# F4.net
KiCad netlist of a schematic drawn in Altium Designer
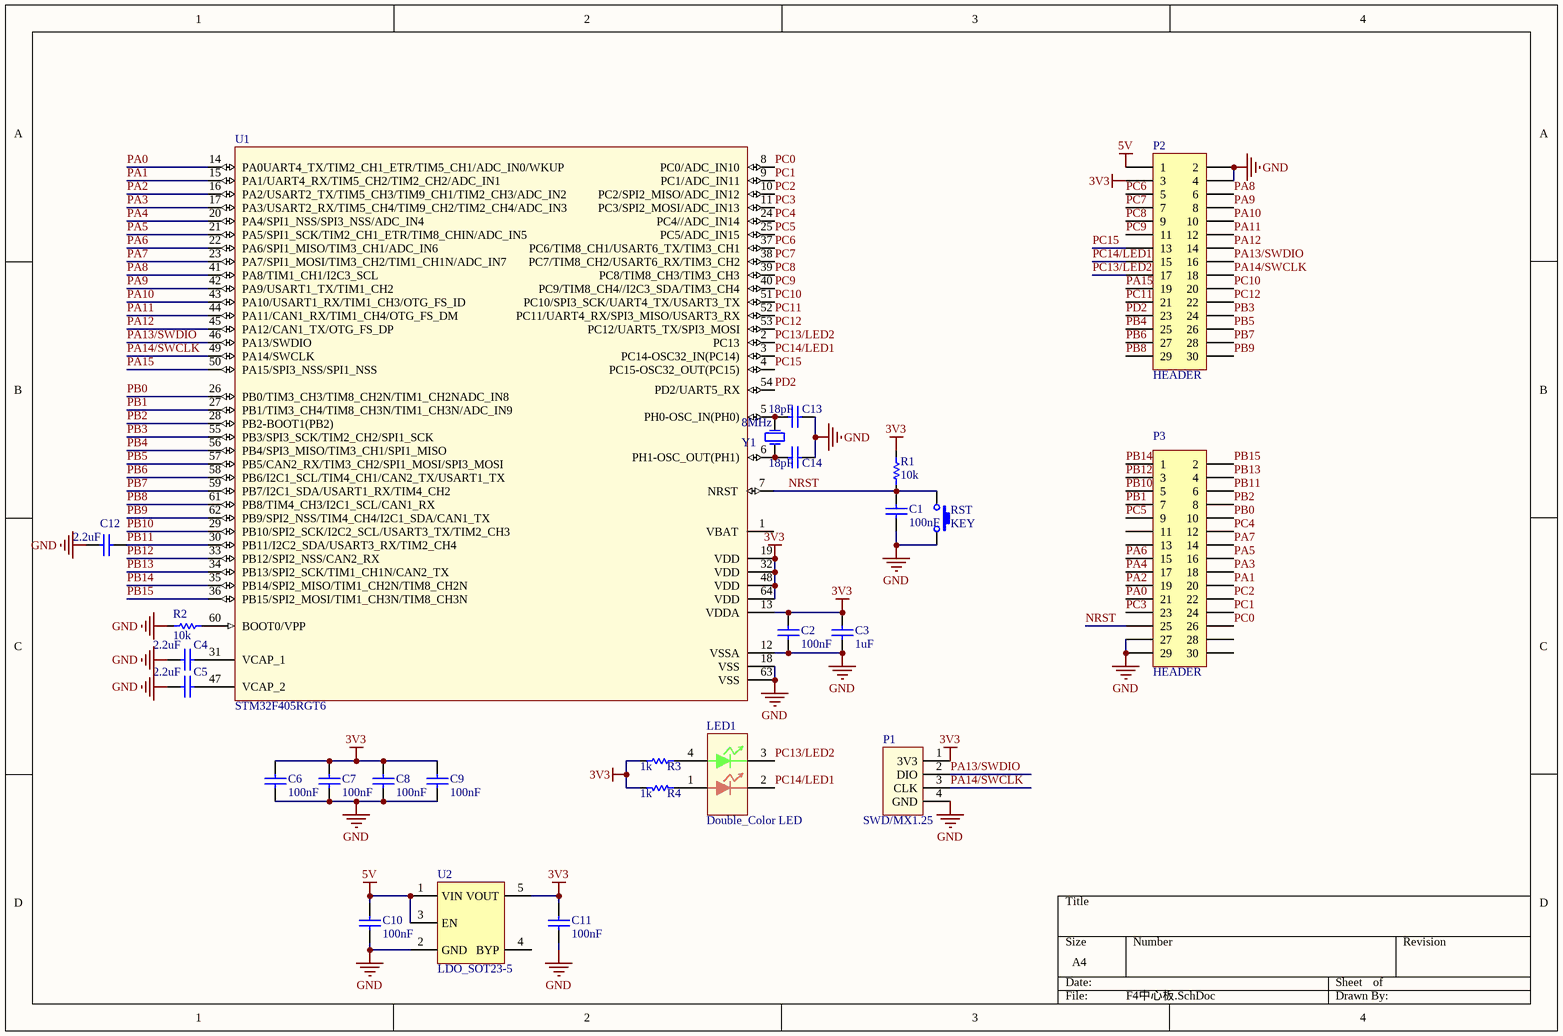
[diagram p0: F4中心板.SchDoc]

(export (version "E")
  (design (tool "Eeschema 10.0.6"))
  (components
    (comp (ref "C1")
      (value "100nF")
      (footprint "0603C")
      (description "Capacitor")
      (fields (field (name "PUBLISHER") "Altium Limited"))
      (libsource (lib "MyComponents_v2.5") (part "Cap"))
    )
    (comp (ref "C2")
      (value "100nF")
      (footprint "0603C")
      (description "Capacitor")
      (fields (field (name "PUBLISHER") "Altium Limited"))
      (libsource (lib "MyComponents_v2.5") (part "Cap"))
    )
    (comp (ref "C3")
      (value "1uF")
      (footprint "0603C")
      (description "Capacitor")
      (fields (field (name "PUBLISHER") "Altium Limited"))
      (libsource (lib "MyComponents_v2.5") (part "Cap"))
    )
    (comp (ref "C4")
      (value "2.2uF")
      (footprint "0603C")
      (description "Capacitor")
      (fields (field (name "PUBLISHER") "Altium Limited"))
      (libsource (lib "MyComponents_v2.5") (part "Cap"))
    )
    (comp (ref "C5")
      (value "2.2uF")
      (footprint "0603C")
      (description "Capacitor")
      (fields (field (name "PUBLISHER") "Altium Limited"))
      (libsource (lib "MyComponents_v2.5") (part "Cap"))
    )
    (comp (ref "C6")
      (value "100nF")
      (footprint "0603C")
      (description "Capacitor")
      (fields (field (name "PUBLISHER") "Altium Limited"))
      (libsource (lib "MyComponents_v2.5") (part "Cap"))
    )
    (comp (ref "C7")
      (value "100nF")
      (footprint "0603C")
      (description "Capacitor")
      (fields (field (name "PUBLISHER") "Altium Limited"))
      (libsource (lib "MyComponents_v2.5") (part "Cap"))
    )
    (comp (ref "C8")
      (value "100nF")
      (footprint "0603C")
      (description "Capacitor")
      (fields (field (name "PUBLISHER") "Altium Limited"))
      (libsource (lib "MyComponents_v2.5") (part "Cap"))
    )
    (comp (ref "C9")
      (value "100nF")
      (footprint "0603C")
      (description "Capacitor")
      (fields (field (name "PUBLISHER") "Altium Limited"))
      (libsource (lib "MyComponents_v2.5") (part "Cap"))
    )
    (comp (ref "C10")
      (value "100nF")
      (footprint "0603C")
      (description "Capacitor")
      (fields (field (name "PUBLISHER") "Altium Limited"))
      (libsource (lib "MyComponents_v2.5") (part "Cap"))
    )
    (comp (ref "C11")
      (value "100nF")
      (footprint "0603C")
      (description "Capacitor")
      (fields (field (name "PUBLISHER") "Altium Limited"))
      (libsource (lib "MyComponents_v2.5") (part "Cap"))
    )
    (comp (ref "C12")
      (value "2.2uF")
      (footprint "0603C")
      (description "Capacitor")
      (fields (field (name "PUBLISHER") "Altium Limited"))
      (libsource (lib "MyComponents_v2.5") (part "Cap"))
    )
    (comp (ref "C13")
      (value "18pF")
      (footprint "0603C")
      (description "Capacitor")
      (fields (field (name "PUBLISHER") "Altium Limited"))
      (libsource (lib "MyComponents_v2.5") (part "Cap"))
    )
    (comp (ref "C14")
      (value "18pF")
      (footprint "0603C")
      (description "Capacitor")
      (fields (field (name "PUBLISHER") "Altium Limited"))
      (libsource (lib "MyComponents_v2.5") (part "Cap"))
    )
    (comp (ref "LED1")
      (value "Double_Color LED")
      (footprint "0805LEDX2")
      (libsource (lib "MyComponents_v2.5") (part "Double_Color LED"))
    )
    (comp (ref "P1")
      (value "SWD/MX1.25")
      (footprint "A1.25AW-4P")
      (libsource (lib "MyComponents_v2.5") (part "SWD_HEADER"))
    )
    (comp (ref "P2")
      (value "HEADER")
      (footprint "HEADER 15x2 SMT 1.27MM")
      (description "15X2 header")
      (libsource (lib "MyComponents_v2.5") (part "HEADER 15x2"))
    )
    (comp (ref "P3")
      (value "HEADER")
      (footprint "HEADER 15x2 SMT 1.27MM")
      (description "15X2 header")
      (libsource (lib "MyComponents_v2.5") (part "HEADER 15x2"))
    )
    (comp (ref "R1")
      (value "10k")
      (footprint "0603R")
      (description "Resistor")
      (fields (field (name "PUBLISHER") "Altium Limited"))
      (libsource (lib "MyComponents_v2.5") (part "Res1"))
    )
    (comp (ref "R2")
      (value "10k")
      (footprint "0603R")
      (description "Resistor")
      (fields (field (name "PUBLISHER") "Altium Limited"))
      (libsource (lib "MyComponents_v2.5") (part "Res1"))
    )
    (comp (ref "R3")
      (value "1k")
      (footprint "0603R")
      (description "Resistor")
      (fields (field (name "PUBLISHER") "Altium Limited"))
      (libsource (lib "MyComponents_v2.5") (part "Res1"))
    )
    (comp (ref "R4")
      (value "1k")
      (footprint "0603R")
      (description "Resistor")
      (fields (field (name "PUBLISHER") "Altium Limited"))
      (libsource (lib "MyComponents_v2.5") (part "Res1"))
    )
    (comp (ref "RST")
      (value "KEY")
      (footprint "SW 3mmx4mm")
      (description "Button")
      (fields (field (name "PUBLISHER") "Altium Limited"))
      (libsource (lib "MyComponents_v2.5") (part "PushButton_2p"))
    )
    (comp (ref "U1")
      (value "STM32F405RGT6")
      (footprint "LQFP_64")
      (libsource (lib "MyComponents_v2.5") (part "STM32F405RGT6_detail_1"))
    )
    (comp (ref "U2")
      (value "LDO_SOT23-5")
      (footprint "SOT-23-5 L")
      (libsource (lib "MyComponents_v2.5") (part "LDO_SOT23-5"))
    )
    (comp (ref "Y1")
      (value "8MHz")
      (footprint "NX3225GD")
      (description "Crystal Oscillator")
      (fields (field (name "PUBLISHER") "Altium Limited"))
      (libsource (lib "MyComponents_v2.5") (part "XTAL"))
    )
  )
  (nets
    (net (code "1") (name "/NRST") (class "Default")
      (node (ref "C1") (pin "2") (pinfunction "2_2") (pintype "passive"))
      (node (ref "P3") (pin "25") (pinfunction "25_25") (pintype "passive"))
      (node (ref "R1") (pin "1") (pinfunction "1_1") (pintype "passive"))
      (node (ref "RST") (pin "1") (pinfunction "1_1") (pintype "passive"))
      (node (ref "U1") (pin "7") (pinfunction "NRST_7") (pintype "bidirectional"))
    )
    (net (code "2") (name "/PA0") (class "Default")
      (node (ref "P3") (pin "21") (pinfunction "21_21") (pintype "passive"))
      (node (ref "U1") (pin "14") (pinfunction "PA0UART4_TX/TIM2_CH1_ETR/TIM5_CH1/ADC_IN0/WKUP_14") (pintype "bidirectional"))
    )
    (net (code "3") (name "/PA1") (class "Default")
      (node (ref "P3") (pin "20") (pinfunction "20_20") (pintype "passive"))
      (node (ref "U1") (pin "15") (pinfunction "PA1/UART4_RX/TIM5_CH2/TIM2_CH2/ADC_IN1_15") (pintype "bidirectional"))
    )
    (net (code "4") (name "/PA2") (class "Default")
      (node (ref "P3") (pin "19") (pinfunction "19_19") (pintype "passive"))
      (node (ref "U1") (pin "16") (pinfunction "PA2/USART2_TX/TIM5_CH3/TIM9_CH1/TIM2_CH3/ADC_IN2_16") (pintype "bidirectional"))
    )
    (net (code "5") (name "/PA3") (class "Default")
      (node (ref "P3") (pin "18") (pinfunction "18_18") (pintype "passive"))
      (node (ref "U1") (pin "17") (pinfunction "PA3/USART2_RX/TIM5_CH4/TIM9_CH2/TIM2_CH4/ADC_IN3_17") (pintype "bidirectional"))
    )
    (net (code "6") (name "/PA4") (class "Default")
      (node (ref "P3") (pin "17") (pinfunction "17_17") (pintype "passive"))
      (node (ref "U1") (pin "20") (pinfunction "PA4/SPI1_NSS/SPI3_NSS/ADC_IN4_20") (pintype "bidirectional"))
    )
    (net (code "7") (name "/PA5") (class "Default")
      (node (ref "P3") (pin "16") (pinfunction "16_16") (pintype "passive"))
      (node (ref "U1") (pin "21") (pinfunction "PA5/SPI1_SCK/TIM2_CH1_ETR/TIM8_CHIN/ADC_IN5_21") (pintype "bidirectional"))
    )
    (net (code "8") (name "/PA6") (class "Default")
      (node (ref "P3") (pin "15") (pinfunction "15_15") (pintype "passive"))
      (node (ref "U1") (pin "22") (pinfunction "PA6/SPI1_MISO/TIM3_CH1/ADC_IN6_22") (pintype "bidirectional"))
    )
    (net (code "9") (name "/PA7") (class "Default")
      (node (ref "P3") (pin "14") (pinfunction "14_14") (pintype "passive"))
      (node (ref "U1") (pin "23") (pinfunction "PA7/SPI1_MOSI/TIM3_CH2/TIM1_CH1N/ADC_IN7_23") (pintype "bidirectional"))
    )
    (net (code "10") (name "/PA8") (class "Default")
      (node (ref "P2") (pin "6") (pinfunction "6_6") (pintype "passive"))
      (node (ref "U1") (pin "41") (pinfunction "PA8/TIM1_CH1/I2C3_SCL_41") (pintype "bidirectional"))
    )
    (net (code "11") (name "/PA9") (class "Default")
      (node (ref "P2") (pin "8") (pinfunction "8_8") (pintype "passive"))
      (node (ref "U1") (pin "42") (pinfunction "PA9/USART1_TX/TIM1_CH2_42") (pintype "bidirectional"))
    )
    (net (code "12") (name "/PA10") (class "Default")
      (node (ref "P2") (pin "10") (pinfunction "10_10") (pintype "passive"))
      (node (ref "U1") (pin "43") (pinfunction "PA10/USART1_RX/TIM1_CH3/OTG_FS_ID_43") (pintype "bidirectional"))
    )
    (net (code "13") (name "/PA11") (class "Default")
      (node (ref "P2") (pin "12") (pinfunction "12_12") (pintype "passive"))
      (node (ref "U1") (pin "44") (pinfunction "PA11/CAN1_RX/TIM1_CH4/OTG_FS_DM_44") (pintype "bidirectional"))
    )
    (net (code "14") (name "/PA12") (class "Default")
      (node (ref "P2") (pin "14") (pinfunction "14_14") (pintype "passive"))
      (node (ref "U1") (pin "45") (pinfunction "PA12/CAN1_TX/OTG_FS_DP_45") (pintype "bidirectional"))
    )
    (net (code "15") (name "/PA13{slash}SWDIO") (class "Default")
      (node (ref "P1") (pin "2") (pinfunction "DIO_2") (pintype "passive"))
      (node (ref "P2") (pin "16") (pinfunction "16_16") (pintype "passive"))
      (node (ref "U1") (pin "46") (pinfunction "PA13/SWDIO_46") (pintype "bidirectional"))
    )
    (net (code "16") (name "/PA14{slash}SWCLK") (class "Default")
      (node (ref "P1") (pin "3") (pinfunction "CLK_3") (pintype "passive"))
      (node (ref "P2") (pin "18") (pinfunction "18_18") (pintype "passive"))
      (node (ref "U1") (pin "49") (pinfunction "PA14/SWCLK_49") (pintype "bidirectional"))
    )
    (net (code "17") (name "/PA15") (class "Default")
      (node (ref "P2") (pin "19") (pinfunction "19_19") (pintype "passive"))
      (node (ref "U1") (pin "50") (pinfunction "PA15/SPI3_NSS/SPI1_NSS_50") (pintype "bidirectional"))
    )
    (net (code "18") (name "/PB0") (class "Default")
      (node (ref "P3") (pin "10") (pinfunction "10_10") (pintype "passive"))
      (node (ref "U1") (pin "26") (pinfunction "PB0/TIM3_CH3/TIM8_CH2N/TIM1_CH2NADC_IN8_26") (pintype "bidirectional"))
    )
    (net (code "19") (name "/PB1") (class "Default")
      (node (ref "P3") (pin "7") (pinfunction "7_7") (pintype "passive"))
      (node (ref "U1") (pin "27") (pinfunction "PB1/TIM3_CH4/TIM8_CH3N/TIM1_CH3N/ADC_IN9_27") (pintype "bidirectional"))
    )
    (net (code "20") (name "/PB2") (class "Default")
      (node (ref "P3") (pin "8") (pinfunction "8_8") (pintype "passive"))
      (node (ref "U1") (pin "28") (pinfunction "PB2-BOOT1(PB2)_28") (pintype "bidirectional"))
    )
    (net (code "21") (name "/PB3") (class "Default")
      (node (ref "P2") (pin "24") (pinfunction "24_24") (pintype "passive"))
      (node (ref "U1") (pin "55") (pinfunction "PB3/SPI3_SCK/TIM2_CH2/SPI1_SCK_55") (pintype "bidirectional"))
    )
    (net (code "22") (name "/PB4") (class "Default")
      (node (ref "P2") (pin "25") (pinfunction "25_25") (pintype "passive"))
      (node (ref "U1") (pin "56") (pinfunction "PB4/SPI3_MISO/TIM3_CH1/SPI1_MISO_56") (pintype "bidirectional"))
    )
    (net (code "23") (name "/PB5") (class "Default")
      (node (ref "P2") (pin "26") (pinfunction "26_26") (pintype "passive"))
      (node (ref "U1") (pin "57") (pinfunction "PB5/CAN2_RX/TIM3_CH2/SPI1_MOSI/SPI3_MOSI_57") (pintype "bidirectional"))
    )
    (net (code "24") (name "/PB6") (class "Default")
      (node (ref "P2") (pin "27") (pinfunction "27_27") (pintype "passive"))
      (node (ref "U1") (pin "58") (pinfunction "PB6/I2C1_SCL/TIM4_CH1/CAN2_TX/USART1_TX_58") (pintype "bidirectional"))
    )
    (net (code "25") (name "/PB7") (class "Default")
      (node (ref "P2") (pin "28") (pinfunction "28_28") (pintype "passive"))
      (node (ref "U1") (pin "59") (pinfunction "PB7/I2C1_SDA/USART1_RX/TIM4_CH2_59") (pintype "bidirectional"))
    )
    (net (code "26") (name "/PB8") (class "Default")
      (node (ref "P2") (pin "29") (pinfunction "29_29") (pintype "passive"))
      (node (ref "U1") (pin "61") (pinfunction "PB8/TIM4_CH3/I2C1_SCL/CAN1_RX_61") (pintype "bidirectional"))
    )
    (net (code "27") (name "/PB9") (class "Default")
      (node (ref "P2") (pin "30") (pinfunction "30_30") (pintype "passive"))
      (node (ref "U1") (pin "62") (pinfunction "PB9/SPI2_NSS/TIM4_CH4/I2C1_SDA/CAN1_TX_62") (pintype "bidirectional"))
    )
    (net (code "28") (name "/PB10") (class "Default")
      (node (ref "P3") (pin "5") (pinfunction "5_5") (pintype "passive"))
      (node (ref "U1") (pin "29") (pinfunction "PB10/SPI2_SCK/I2C2_SCL/USART3_TX/TIM2_CH3_29") (pintype "bidirectional"))
    )
    (net (code "29") (name "/PB11") (class "Default")
      (node (ref "C12") (pin "2") (pinfunction "2_2") (pintype "passive"))
      (node (ref "P3") (pin "6") (pinfunction "6_6") (pintype "passive"))
      (node (ref "U1") (pin "30") (pinfunction "PB11/I2C2_SDA/USART3_RX/TIM2_CH4_30") (pintype "bidirectional"))
    )
    (net (code "30") (name "/PB12") (class "Default")
      (node (ref "P3") (pin "3") (pinfunction "3_3") (pintype "passive"))
      (node (ref "U1") (pin "33") (pinfunction "PB12/SPI2_NSS/CAN2_RX_33") (pintype "bidirectional"))
    )
    (net (code "31") (name "/PB13") (class "Default")
      (node (ref "P3") (pin "4") (pinfunction "4_4") (pintype "passive"))
      (node (ref "U1") (pin "34") (pinfunction "PB13/SPI2_SCK/TIM1_CH1N/CAN2_TX_34") (pintype "bidirectional"))
    )
    (net (code "32") (name "/PB14") (class "Default")
      (node (ref "P3") (pin "1") (pinfunction "1_1") (pintype "passive"))
      (node (ref "U1") (pin "35") (pinfunction "PB14/SPI2_MISO/TIM1_CH2N/TIM8_CH2N_35") (pintype "bidirectional"))
    )
    (net (code "33") (name "/PB15") (class "Default")
      (node (ref "P3") (pin "2") (pinfunction "2_2") (pintype "passive"))
      (node (ref "U1") (pin "36") (pinfunction "PB15/SPI2_MOSI/TIM1_CH3N/TIM8_CH3N_36") (pintype "bidirectional"))
    )
    (net (code "34") (name "/PC0") (class "Default")
      (node (ref "P3") (pin "26") (pinfunction "26_26") (pintype "passive"))
      (node (ref "U1") (pin "8") (pinfunction "PC0/ADC_IN10_8") (pintype "bidirectional"))
    )
    (net (code "35") (name "/PC1") (class "Default")
      (node (ref "P3") (pin "24") (pinfunction "24_24") (pintype "passive"))
      (node (ref "U1") (pin "9") (pinfunction "PC1/ADC_IN11_9") (pintype "bidirectional"))
    )
    (net (code "36") (name "/PC2") (class "Default")
      (node (ref "P3") (pin "22") (pinfunction "22_22") (pintype "passive"))
      (node (ref "U1") (pin "10") (pinfunction "PC2/SPI2_MISO/ADC_IN12_10") (pintype "bidirectional"))
    )
    (net (code "37") (name "/PC3") (class "Default")
      (node (ref "P3") (pin "23") (pinfunction "23_23") (pintype "passive"))
      (node (ref "U1") (pin "11") (pinfunction "PC3/SPI2_MOSI/ADC_IN13_11") (pintype "bidirectional"))
    )
    (net (code "38") (name "/PC4") (class "Default")
      (node (ref "P3") (pin "12") (pinfunction "12_12") (pintype "passive"))
      (node (ref "U1") (pin "24") (pinfunction "PC4//ADC_IN14_24") (pintype "bidirectional"))
    )
    (net (code "39") (name "/PC5") (class "Default")
      (node (ref "P3") (pin "9") (pinfunction "9_9") (pintype "passive"))
      (node (ref "U1") (pin "25") (pinfunction "PC5/ADC_IN15_25") (pintype "bidirectional"))
    )
    (net (code "40") (name "/PC6") (class "Default")
      (node (ref "P2") (pin "5") (pinfunction "5_5") (pintype "passive"))
      (node (ref "U1") (pin "37") (pinfunction "PC6/TIM8_CH1/USART6_TX/TIM3_CH1_37") (pintype "bidirectional"))
    )
    (net (code "41") (name "/PC7") (class "Default")
      (node (ref "P2") (pin "7") (pinfunction "7_7") (pintype "passive"))
      (node (ref "U1") (pin "38") (pinfunction "PC7/TIM8_CH2/USART6_RX/TIM3_CH2_38") (pintype "bidirectional"))
    )
    (net (code "42") (name "/PC8") (class "Default")
      (node (ref "P2") (pin "9") (pinfunction "9_9") (pintype "passive"))
      (node (ref "U1") (pin "39") (pinfunction "PC8/TIM8_CH3/TIM3_CH3_39") (pintype "bidirectional"))
    )
    (net (code "43") (name "/PC9") (class "Default")
      (node (ref "P2") (pin "11") (pinfunction "11_11") (pintype "passive"))
      (node (ref "U1") (pin "40") (pinfunction "PC9/TIM8_CH4//I2C3_SDA/TIM3_CH4_40") (pintype "bidirectional"))
    )
    (net (code "44") (name "/PC10") (class "Default")
      (node (ref "P2") (pin "20") (pinfunction "20_20") (pintype "passive"))
      (node (ref "U1") (pin "51") (pinfunction "PC10/SPI3_SCK/UART4_TX/USART3_TX_51") (pintype "bidirectional"))
    )
    (net (code "45") (name "/PC11") (class "Default")
      (node (ref "P2") (pin "21") (pinfunction "21_21") (pintype "passive"))
      (node (ref "U1") (pin "52") (pinfunction "PC11/UART4_RX/SPI3_MISO/USART3_RX_52") (pintype "bidirectional"))
    )
    (net (code "46") (name "/PC12") (class "Default")
      (node (ref "P2") (pin "22") (pinfunction "22_22") (pintype "passive"))
      (node (ref "U1") (pin "53") (pinfunction "PC12/UART5_TX/SPI3_MOSI_53") (pintype "bidirectional"))
    )
    (net (code "47") (name "/PC13{slash}LED2") (class "Default")
      (node (ref "LED1") (pin "3") (pinfunction "3_3") (pintype "passive"))
      (node (ref "P2") (pin "17") (pinfunction "17_17") (pintype "passive"))
      (node (ref "U1") (pin "2") (pinfunction "PC13_2") (pintype "bidirectional"))
    )
    (net (code "48") (name "/PC14{slash}LED1") (class "Default")
      (node (ref "LED1") (pin "2") (pinfunction "2_2") (pintype "passive"))
      (node (ref "P2") (pin "15") (pinfunction "15_15") (pintype "passive"))
      (node (ref "U1") (pin "3") (pinfunction "PC14-OSC32_IN(PC14)_3") (pintype "bidirectional"))
    )
    (net (code "49") (name "/PC15") (class "Default")
      (node (ref "P2") (pin "13") (pinfunction "13_13") (pintype "passive"))
      (node (ref "U1") (pin "4") (pinfunction "PC15-OSC32_OUT(PC15)_4") (pintype "bidirectional"))
    )
    (net (code "50") (name "/PD2") (class "Default")
      (node (ref "P2") (pin "23") (pinfunction "23_23") (pintype "passive"))
      (node (ref "U1") (pin "54") (pinfunction "PD2/UART5_RX_54") (pintype "bidirectional"))
    )
    (net (code "51") (name "3V3") (class "Default")
      (node (ref "C11") (pin "2") (pinfunction "2_2") (pintype "passive"))
      (node (ref "C2") (pin "2") (pinfunction "2_2") (pintype "passive"))
      (node (ref "C3") (pin "2") (pinfunction "2_2") (pintype "passive"))
      (node (ref "C6") (pin "2") (pinfunction "2_2") (pintype "passive"))
      (node (ref "C7") (pin "2") (pinfunction "2_2") (pintype "passive"))
      (node (ref "C8") (pin "2") (pinfunction "2_2") (pintype "passive"))
      (node (ref "C9") (pin "2") (pinfunction "2_2") (pintype "passive"))
      (node (ref "P1") (pin "1") (pinfunction "3V3_1") (pintype "passive"))
      (node (ref "P2") (pin "3") (pinfunction "3_3") (pintype "passive"))
      (node (ref "R1") (pin "2") (pinfunction "2_2") (pintype "passive"))
      (node (ref "R3") (pin "2") (pinfunction "2_2") (pintype "passive"))
      (node (ref "R4") (pin "1") (pinfunction "1_1") (pintype "passive"))
      (node (ref "U1") (pin "13") (pinfunction "VDDA_13") (pintype "power_in"))
      (node (ref "U1") (pin "19") (pinfunction "VDD_19") (pintype "power_in"))
      (node (ref "U1") (pin "32") (pinfunction "VDD_32") (pintype "power_in"))
      (node (ref "U1") (pin "48") (pinfunction "VDD_48") (pintype "power_in"))
      (node (ref "U1") (pin "64") (pinfunction "VDD_64") (pintype "power_in"))
      (node (ref "U2") (pin "5") (pinfunction "VOUT_5") (pintype "passive"))
    )
    (net (code "52") (name "5V") (class "Default")
      (node (ref "C10") (pin "2") (pinfunction "2_2") (pintype "passive"))
      (node (ref "P2") (pin "1") (pinfunction "1_1") (pintype "passive"))
      (node (ref "U2") (pin "1") (pinfunction "VIN_1") (pintype "passive"))
      (node (ref "U2") (pin "3") (pinfunction "EN_3") (pintype "passive"))
    )
    (net (code "53") (name "GND") (class "Default")
      (node (ref "C1") (pin "1") (pinfunction "1_1") (pintype "passive"))
      (node (ref "C10") (pin "1") (pinfunction "1_1") (pintype "passive"))
      (node (ref "C11") (pin "1") (pinfunction "1_1") (pintype "passive"))
      (node (ref "C12") (pin "1") (pinfunction "1_1") (pintype "passive"))
      (node (ref "C13") (pin "1") (pinfunction "1_1") (pintype "passive"))
      (node (ref "C14") (pin "1") (pinfunction "1_1") (pintype "passive"))
      (node (ref "C2") (pin "1") (pinfunction "1_1") (pintype "passive"))
      (node (ref "C3") (pin "1") (pinfunction "1_1") (pintype "passive"))
      (node (ref "C4") (pin "1") (pinfunction "1_1") (pintype "passive"))
      (node (ref "C5") (pin "1") (pinfunction "1_1") (pintype "passive"))
      (node (ref "C6") (pin "1") (pinfunction "1_1") (pintype "passive"))
      (node (ref "C7") (pin "1") (pinfunction "1_1") (pintype "passive"))
      (node (ref "C8") (pin "1") (pinfunction "1_1") (pintype "passive"))
      (node (ref "C9") (pin "1") (pinfunction "1_1") (pintype "passive"))
      (node (ref "P1") (pin "4") (pinfunction "GND_4") (pintype "passive"))
      (node (ref "P2") (pin "2") (pinfunction "2_2") (pintype "passive"))
      (node (ref "P2") (pin "4") (pinfunction "4_4") (pintype "passive"))
      (node (ref "P3") (pin "27") (pinfunction "27_27") (pintype "passive"))
      (node (ref "P3") (pin "29") (pinfunction "29_29") (pintype "passive"))
      (node (ref "R2") (pin "1") (pinfunction "1_1") (pintype "passive"))
      (node (ref "RST") (pin "2") (pinfunction "2_2") (pintype "passive"))
      (node (ref "U1") (pin "12") (pinfunction "VSSA_12") (pintype "power_in"))
      (node (ref "U1") (pin "18") (pinfunction "VSS_18") (pintype "power_in"))
      (node (ref "U1") (pin "63") (pinfunction "VSS_63") (pintype "power_in"))
      (node (ref "U2") (pin "2") (pinfunction "GND_2") (pintype "passive"))
    )
    (net (code "54") (name "Net-(LED1-Pad1)") (class "Default")
      (node (ref "LED1") (pin "1") (pinfunction "1_1") (pintype "passive"))
      (node (ref "R4") (pin "2") (pinfunction "2_2") (pintype "passive"))
    )
    (net (code "55") (name "Net-(LED1-Pad4)") (class "Default")
      (node (ref "LED1") (pin "4") (pinfunction "4_4") (pintype "passive"))
      (node (ref "R3") (pin "1") (pinfunction "1_1") (pintype "passive"))
    )
    (net (code "56") (name "Net-(U1-BOOT0{slash}VPP)") (class "Default")
      (node (ref "R2") (pin "2") (pinfunction "2_2") (pintype "passive"))
      (node (ref "U1") (pin "60") (pinfunction "BOOT0/VPP_60") (pintype "input"))
    )
    (net (code "57") (name "Net-(U1-PH0-OSC_IN(PH0))") (class "Default")
      (node (ref "C13") (pin "2") (pinfunction "2_2") (pintype "passive"))
      (node (ref "U1") (pin "5") (pinfunction "PH0-OSC_IN(PH0)_5") (pintype "bidirectional"))
      (node (ref "Y1") (pin "2") (pinfunction "OSC2_2") (pintype "passive"))
    )
    (net (code "58") (name "Net-(U1-PH1-OSC_OUT(PH1))") (class "Default")
      (node (ref "C14") (pin "2") (pinfunction "2_2") (pintype "passive"))
      (node (ref "U1") (pin "6") (pinfunction "PH1-OSC_OUT(PH1)_6") (pintype "bidirectional"))
      (node (ref "Y1") (pin "1") (pinfunction "OSC1_1") (pintype "passive"))
    )
    (net (code "59") (name "Net-(U1-VCAP_1)") (class "Default")
      (node (ref "C4") (pin "2") (pinfunction "2_2") (pintype "passive"))
      (node (ref "U1") (pin "31") (pinfunction "VCAP_1_31") (pintype "power_in"))
    )
    (net (code "60") (name "Net-(U1-VCAP_2)") (class "Default")
      (node (ref "C5") (pin "2") (pinfunction "2_2") (pintype "passive"))
      (node (ref "U1") (pin "47") (pinfunction "VCAP_2_47") (pintype "power_in"))
    )
    (net (code "61") (name "unconnected-(P3-Pad11)") (class "Default")
      (node (ref "P3") (pin "11") (pinfunction "11_11") (pintype "passive"))
    )
    (net (code "62") (name "unconnected-(P3-Pad13)") (class "Default")
      (node (ref "P3") (pin "13") (pinfunction "13_13") (pintype "passive"))
    )
    (net (code "63") (name "unconnected-(P3-Pad28)") (class "Default")
      (node (ref "P3") (pin "28") (pinfunction "28_28") (pintype "passive"))
    )
    (net (code "64") (name "unconnected-(P3-Pad30)") (class "Default")
      (node (ref "P3") (pin "30") (pinfunction "30_30") (pintype "passive"))
    )
    (net (code "65") (name "unconnected-(U1-VBAT-Pad1)") (class "Default")
      (node (ref "U1") (pin "1") (pinfunction "VBAT_1") (pintype "power_in"))
    )
    (net (code "66") (name "unconnected-(U2-BYP-Pad4)") (class "Default")
      (node (ref "U2") (pin "4") (pinfunction "BYP_4") (pintype "passive"))
    )
  )
)
